# Compute_Module_EXT_INTERFACES.net
KiCad netlist of a schematic drawn in Altium Designer
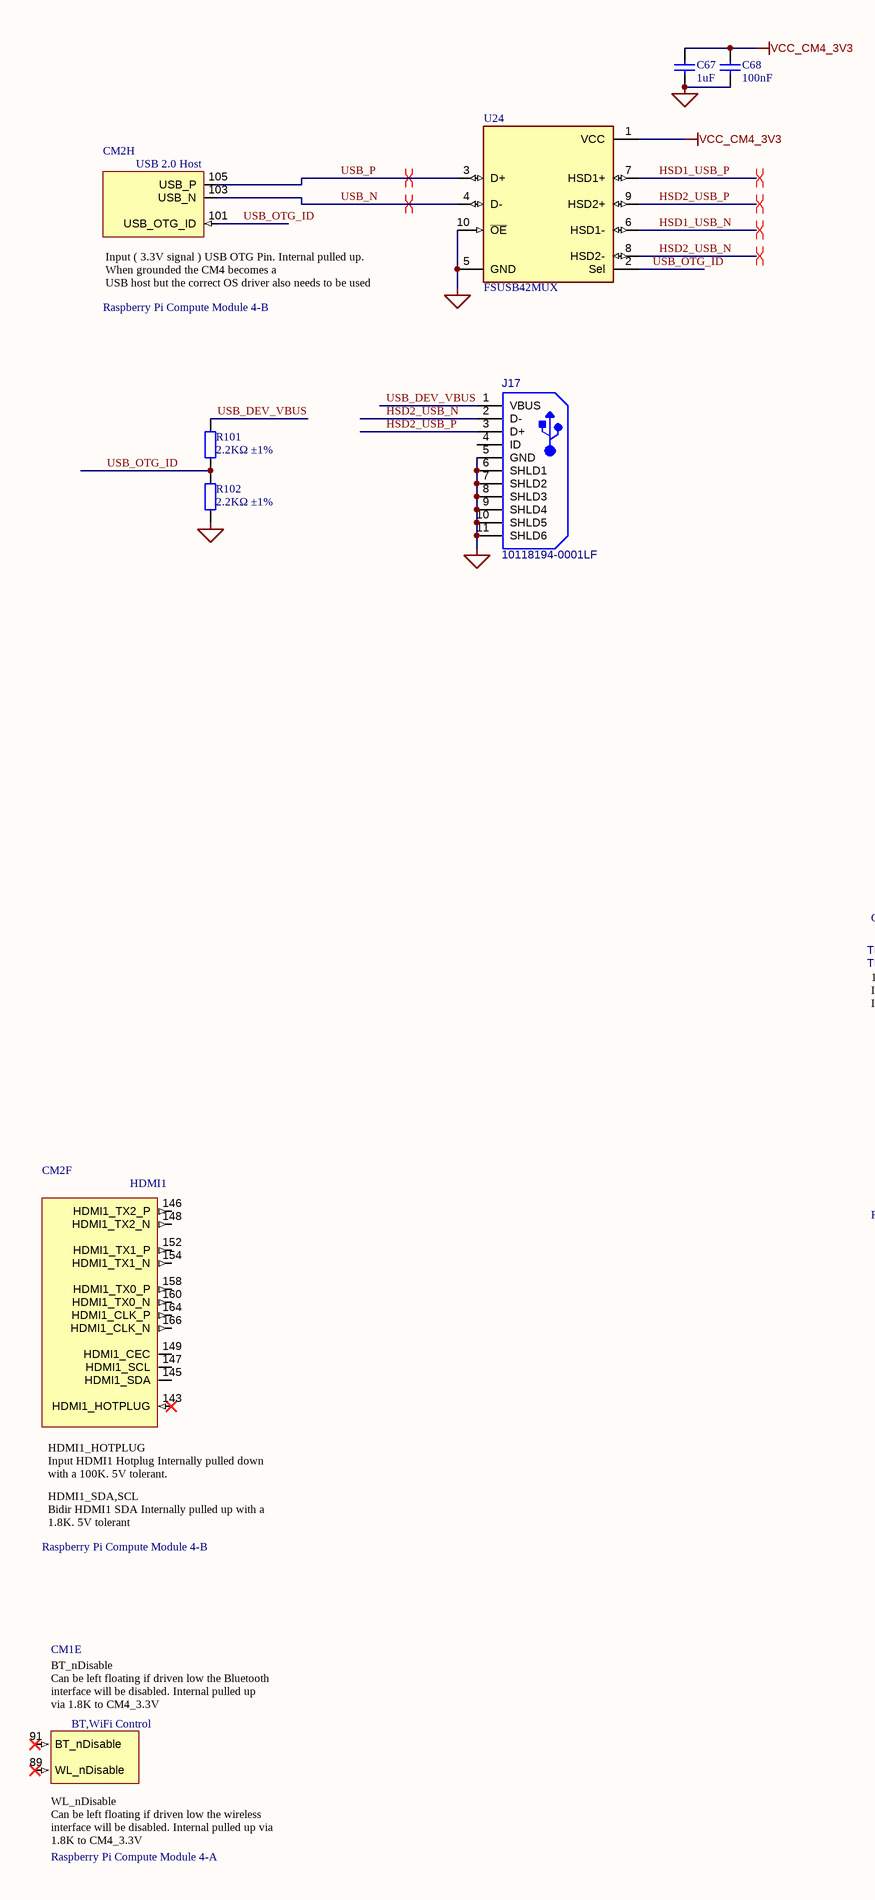
[diagram p0: Compute_Module_EXT_INTERFACES.SchDoc, left]
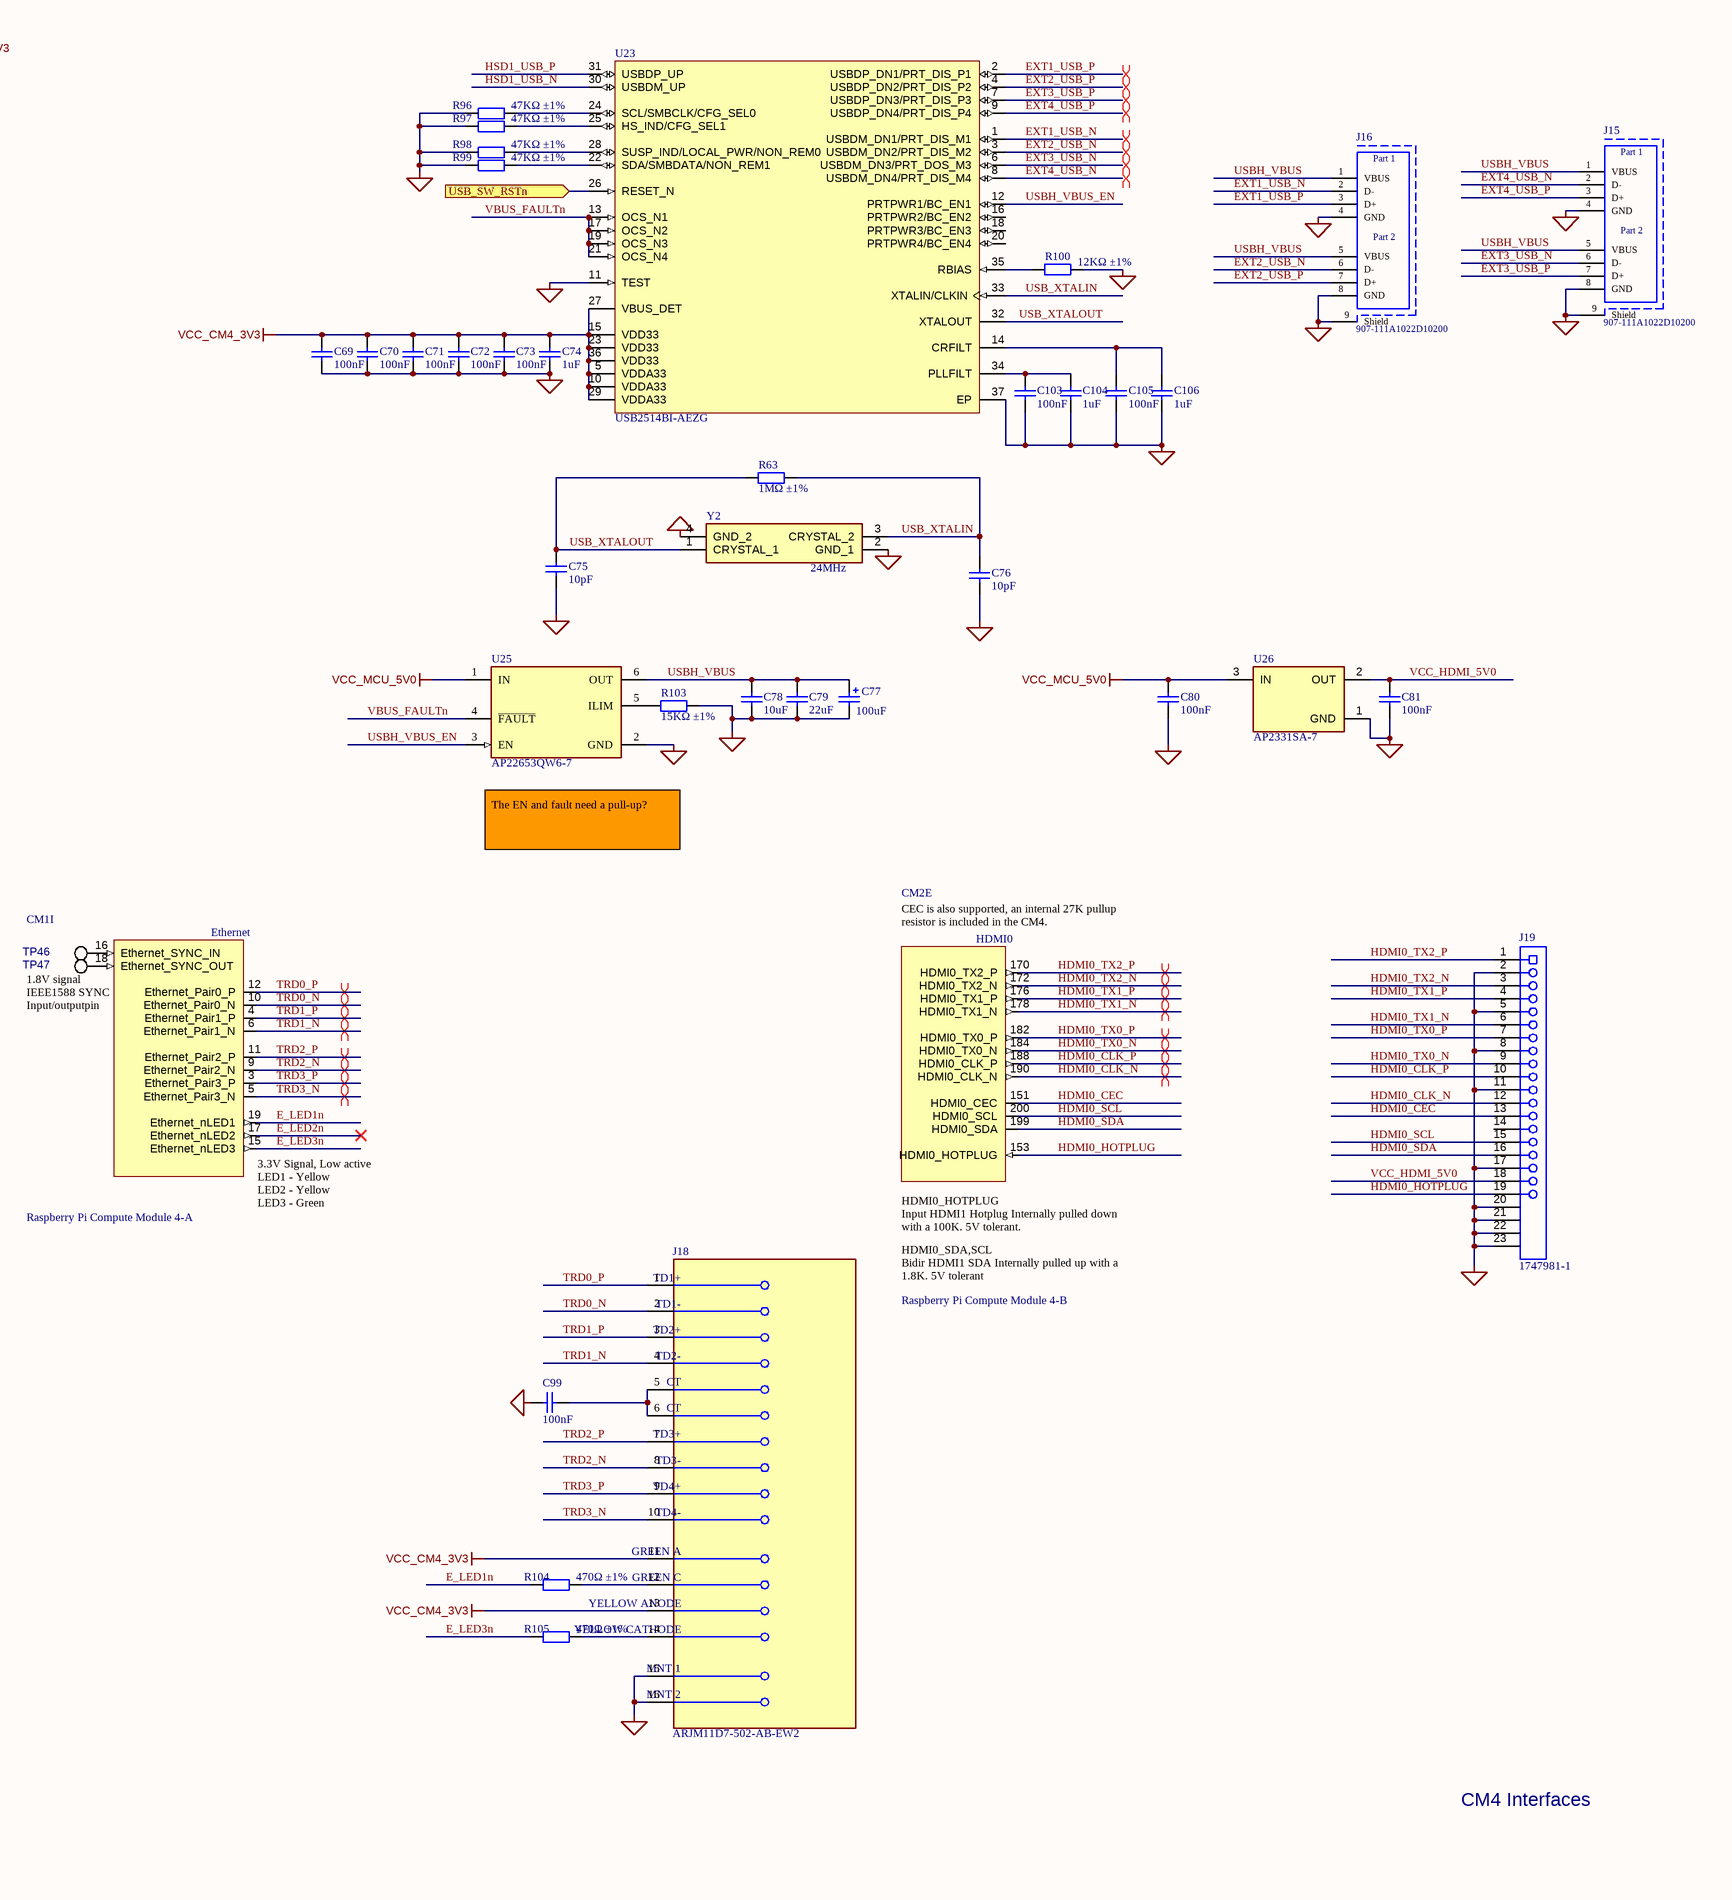
[diagram p1: Compute_Module_EXT_INTERFACES.SchDoc, right]

(export (version "E")
  (design (tool "Eeschema 10.0.6"))
  (components
    (comp (ref "C67")
      (value "1uF")
      (footprint "0603_C")
      (description "Chip capacitors")
      (fields
        (field (name "MANUFACTURER") "Samsung Electro-Mechanics")
        (field (name "MANUFACTURER PART NUMBER") "CL10A105KB8NNNC")
      )
      (libsource (lib "Cap") (part "0603 1uF (105) 10% 50V"))
    )
    (comp (ref "C68")
      (value "100nF")
      (footprint "0603_C")
      (description "Chip capacitors")
      (fields
        (field (name "MANUFACTURER") "YAGEO")
        (field (name "MANUFACTURER PART NUMBER") "CC0603KRX7R9BB104")
      )
      (libsource (lib "Cap") (part "0603 100nF (104) 10% 50V"))
    )
    (comp (ref "C69")
      (value "100nF")
      (footprint "0603_C")
      (description "Chip capacitors")
      (fields
        (field (name "MANUFACTURER") "YAGEO")
        (field (name "MANUFACTURER PART NUMBER") "CC0603KRX7R9BB104")
      )
      (libsource (lib "Cap") (part "0603 100nF (104) 10% 50V"))
    )
    (comp (ref "C70")
      (value "100nF")
      (footprint "0603_C")
      (description "Chip capacitors")
      (fields
        (field (name "MANUFACTURER") "YAGEO")
        (field (name "MANUFACTURER PART NUMBER") "CC0603KRX7R9BB104")
      )
      (libsource (lib "Cap") (part "0603 100nF (104) 10% 50V"))
    )
    (comp (ref "C71")
      (value "100nF")
      (footprint "0603_C")
      (description "Chip capacitors")
      (fields
        (field (name "MANUFACTURER") "YAGEO")
        (field (name "MANUFACTURER PART NUMBER") "CC0603KRX7R9BB104")
      )
      (libsource (lib "Cap") (part "0603 100nF (104) 10% 50V"))
    )
    (comp (ref "C72")
      (value "100nF")
      (footprint "0603_C")
      (description "Chip capacitors")
      (fields
        (field (name "MANUFACTURER") "YAGEO")
        (field (name "MANUFACTURER PART NUMBER") "CC0603KRX7R9BB104")
      )
      (libsource (lib "Cap") (part "0603 100nF (104) 10% 50V"))
    )
    (comp (ref "C73")
      (value "100nF")
      (footprint "0603_C")
      (description "Chip capacitors")
      (fields
        (field (name "MANUFACTURER") "YAGEO")
        (field (name "MANUFACTURER PART NUMBER") "CC0603KRX7R9BB104")
      )
      (libsource (lib "Cap") (part "0603 100nF (104) 10% 50V"))
    )
    (comp (ref "C74")
      (value "1uF")
      (footprint "0603_C")
      (description "Chip capacitors")
      (fields
        (field (name "MANUFACTURER") "Samsung Electro-Mechanics")
        (field (name "MANUFACTURER PART NUMBER") "CL10A105KB8NNNC")
      )
      (libsource (lib "Cap") (part "0603 1uF (105) 10% 50V"))
    )
    (comp (ref "C75")
      (value "10pF")
      (footprint "0603_C")
      (description "Chip capacitors")
      (fields
        (field (name "MANUFACTURER") "Samsung Electro-Mechanics")
        (field (name "PARTNUMBER") "CL10C100JB8NNNC")
      )
      (libsource (lib "Cap") (part "0603 10pF (100) 5% 50V"))
    )
    (comp (ref "C76")
      (value "10pF")
      (footprint "0603_C")
      (description "Chip capacitors")
      (fields
        (field (name "MANUFACTURER") "Samsung Electro-Mechanics")
        (field (name "PARTNUMBER") "CL10C100JB8NNNC")
      )
      (libsource (lib "Cap") (part "0603 10pF (100) 5% 50V"))
    )
    (comp (ref "C77")
      (value "100uF")
      (footprint "WCAP-ASLI_D6.3H7.7")
      (fields
        (field (name "MANUFACTURER") "Capxon International Elec")
        (field (name "MANUFACTURER PART NUMBER") "HV101M035E077ETR")
      )
      (libsource (lib "IQAnalog") (part "865080445010"))
    )
    (comp (ref "C78")
      (value "10uF")
      (footprint "1206_C")
      (description "Chip capacitors")
      (fields
        (field (name "MANUFACTURER") "Samsung Electro-Mechanics")
        (field (name "MANUFACTURER PART NUMBER") "CL31A106KBHNNNE")
      )
      (libsource (lib "Cap") (part "1206 10uF (106) 10% 50V"))
    )
    (comp (ref "C79")
      (value "22uF")
      (footprint "0805_C")
      (description "Chip capacitors")
      (fields
        (field (name "MANUFACTURER") "Samsung Electro-Mechanics")
        (field (name "PARTNUMBER") "CL21A226MAQNNNE")
      )
      (libsource (lib "Cap") (part "0805 22uF (226) 20% 25V"))
    )
    (comp (ref "C80")
      (value "100nF")
      (footprint "0603_C")
      (description "Chip capacitors")
      (fields
        (field (name "MANUFACTURER") "YAGEO")
        (field (name "MANUFACTURER PART NUMBER") "CC0603KRX7R9BB104")
      )
      (libsource (lib "Cap") (part "0603 100nF (104) 10% 50V"))
    )
    (comp (ref "C81")
      (value "100nF")
      (footprint "0603_C")
      (description "Chip capacitors")
      (fields
        (field (name "MANUFACTURER") "YAGEO")
        (field (name "MANUFACTURER PART NUMBER") "CC0603KRX7R9BB104")
      )
      (libsource (lib "Cap") (part "0603 100nF (104) 10% 50V"))
    )
    (comp (ref "C99")
      (value "100nF")
      (footprint "0603_C")
      (description "Chip capacitors")
      (fields
        (field (name "MANUFACTURER") "YAGEO")
        (field (name "MANUFACTURER PART NUMBER") "CC0603KRX7R9BB104")
      )
      (libsource (lib "Cap") (part "0603 100nF (104) 10% 50V"))
    )
    (comp (ref "C103")
      (value "100nF")
      (footprint "0603_C")
      (description "Chip capacitors")
      (fields
        (field (name "MANUFACTURER") "YAGEO")
        (field (name "MANUFACTURER PART NUMBER") "CC0603KRX7R9BB104")
      )
      (libsource (lib "Cap") (part "0603 100nF (104) 10% 50V"))
    )
    (comp (ref "C104")
      (value "1uF")
      (footprint "0603_C")
      (description "Chip capacitors")
      (fields
        (field (name "MANUFACTURER") "Samsung Electro-Mechanics")
        (field (name "MANUFACTURER PART NUMBER") "CL10A105KB8NNNC")
      )
      (libsource (lib "Cap") (part "0603 1uF (105) 10% 50V"))
    )
    (comp (ref "C105")
      (value "100nF")
      (footprint "0603_C")
      (description "Chip capacitors")
      (fields
        (field (name "MANUFACTURER") "YAGEO")
        (field (name "MANUFACTURER PART NUMBER") "CC0603KRX7R9BB104")
      )
      (libsource (lib "Cap") (part "0603 100nF (104) 10% 50V"))
    )
    (comp (ref "C106")
      (value "1uF")
      (footprint "0603_C")
      (description "Chip capacitors")
      (fields
        (field (name "MANUFACTURER") "Samsung Electro-Mechanics")
        (field (name "MANUFACTURER PART NUMBER") "CL10A105KB8NNNC")
      )
      (libsource (lib "Cap") (part "0603 1uF (105) 10% 50V"))
    )
    (comp (ref "CM1")
      (value "Raspberry Pi Compute Module 4-A")
      (footprint "DF40HC30100DS04V51")
      (description "Raspberry Pi Compute Module 4 Pins 1-100 (Connector A)")
      (fields
        (field (name "MANUFACTURER") "Hirose")
        (field (name "MANUFACTURER PART NUMBER") "DF40HC(3.0)-100DS-0.4V(51)")
      )
      (libsource (lib "Sienci_Labs") (part "CM4_Module_A"))
    )
    (comp (ref "CM2")
      (value "Raspberry Pi Compute Module 4-B")
      (footprint "DF40HC30100DS04V51 - p101-200")
      (description "Raspberry Pi Compute Module 4 Pins 101-200 (Connector B)")
      (fields
        (field (name "MANUFACTURER") "Hirose")
        (field (name "MANUFACTURER PART NUMBER") "DF40HC(3.0)-100DS-0.4V(51)")
      )
      (libsource (lib "Sienci_Labs") (part "CM4_Module_B"))
    )
    (comp (ref "J15")
      (value "907-111A1022D10200")
      (footprint "USB-A-TH_USB-M-51")
      (description "USB 2.0 2 8 Female Type-A Plugin USB Connectors ROHS")
      (fields (field (name "MANUFACTURER") "Jing Extension of the Electronic Co."))
      (libsource (lib "Sienci_Labs") (part "907-111A1022D10200"))
    )
    (comp (ref "J16")
      (value "907-111A1022D10200")
      (footprint "USB-A-TH_USB-M-51")
      (description "USB 2.0 2 8 Female Type-A Plugin USB Connectors ROHS")
      (fields (field (name "MANUFACTURER") "Jing Extension of the Electronic Co."))
      (libsource (lib "Sienci_Labs") (part "907-111A1022D10200"))
    )
    (comp (ref "J17")
      (value "10118194-0001LF")
      (footprint "FCI-10118194-0001LF-5_V")
      (description "CONN RCPT USB2.0 MICRO B SMD R/A")
      (fields (field (name "MANUFACTURER") "Amphenol ICC (FCI)"))
      (libsource (lib "Sienci_Labs") (part "USB-5-6SHLD"))
    )
    (comp (ref "J18")
      (value "ARJM11D7-502-AB-EW2")
      (footprint "FP-ARJM11D7-502-AB-EW2-MFG")
      (description "1 Port RJ45Through Hole 10/100/1000 Base-T, AutoMDIX")
      (fields (field (name "MANUFACTURER") "Abracon LLC"))
      (libsource (lib "Sienci_Labs") (part "ARJM11D7-502-AB-EW2"))
    )
    (comp (ref "J19")
      (value "1747981-1")
      (footprint "TE-1747981-1_V")
      (description "HDMI Receptacle, Pitch 0.5 mm, 19 Position, Height 6.38 mm, RoHS, Tape and Reel")
      (fields (field (name "TOLERANCE") "1%") (field (name "MANUFACTURER") "TE Connectivity"))
      (libsource (lib "Altium Content Vault") (part "CN-1P-F-HD19"))
    )
    (comp (ref "R63")
      (value "1MΩ ±1%")
      (footprint "0402_R")
      (description "Chip resistor")
      (fields (field (name "MANUFACTURER") "Uniroyal Elec") (field (name "PARTNUMBER") "0402WGF1004TCE"))
      (libsource (lib "RES") (part "0402 1M (1004) 1%"))
    )
    (comp (ref "R96")
      (value "47KΩ ±1%")
      (footprint "0402_R")
      (description "Chip resistor")
      (fields (field (name "MANUFACTURER") "Uniroyal Elec") (field (name "PARTNUMBER") "0402WGF4702TCE"))
      (libsource (lib "RES") (part "0402 47K (4702) 1%"))
    )
    (comp (ref "R97")
      (value "47KΩ ±1%")
      (footprint "0402_R")
      (description "Chip resistor")
      (fields (field (name "MANUFACTURER") "Uniroyal Elec") (field (name "PARTNUMBER") "0402WGF4702TCE"))
      (libsource (lib "RES") (part "0402 47K (4702) 1%"))
    )
    (comp (ref "R98")
      (value "47KΩ ±1%")
      (footprint "0402_R")
      (description "Chip resistor")
      (fields (field (name "MANUFACTURER") "Uniroyal Elec") (field (name "PARTNUMBER") "0402WGF4702TCE"))
      (libsource (lib "RES") (part "0402 47K (4702) 1%"))
    )
    (comp (ref "R99")
      (value "47KΩ ±1%")
      (footprint "0402_R")
      (description "Chip resistor")
      (fields (field (name "MANUFACTURER") "Uniroyal Elec") (field (name "PARTNUMBER") "0402WGF4702TCE"))
      (libsource (lib "RES") (part "0402 47K (4702) 1%"))
    )
    (comp (ref "R100")
      (value "12KΩ ±1%")
      (footprint "0402_R")
      (description "Chip resistor")
      (fields (field (name "MANUFACTURER") "Uniroyal Elec") (field (name "PARTNUMBER") "0402WGF1202TCE"))
      (libsource (lib "RES") (part "0402 12K (1202) 1%"))
    )
    (comp (ref "R101")
      (value "2.2KΩ ±1%")
      (footprint "0402_R")
      (description "Chip resistor")
      (fields (field (name "MANUFACTURER") "Uniroyal Elec") (field (name "PARTNUMBER") "0402WGF2201TCE"))
      (libsource (lib "RES") (part "0402 2.2K (2201) 1%"))
    )
    (comp (ref "R102")
      (value "2.2KΩ ±1%")
      (footprint "0402_R")
      (description "Chip resistor")
      (fields (field (name "MANUFACTURER") "Uniroyal Elec") (field (name "PARTNUMBER") "0402WGF2201TCE"))
      (libsource (lib "RES") (part "0402 2.2K (2201) 1%"))
    )
    (comp (ref "R103")
      (value "15KΩ ±1%")
      (footprint "0402_R")
      (description "Chip resistor")
      (fields (field (name "MANUFACTURER") "Uniroyal Elec") (field (name "PARTNUMBER") "0402WGF1502TCE"))
      (libsource (lib "RES") (part "0402 15K (1502) 1%"))
    )
    (comp (ref "R104")
      (value "470Ω ±1%")
      (footprint "0402_R")
      (description "Chip resistor")
      (fields (field (name "MANUFACTURER") "Uniroyal Elec") (field (name "PARTNUMBER") "0402WGF4700TCE"))
      (libsource (lib "RES") (part "0402 470R (4700) 1%"))
    )
    (comp (ref "R105")
      (value "470Ω ±1%")
      (footprint "0402_R")
      (description "Chip resistor")
      (fields (field (name "MANUFACTURER") "Uniroyal Elec") (field (name "PARTNUMBER") "0402WGF4700TCE"))
      (libsource (lib "RES") (part "0402 470R (4700) 1%"))
    )
    (comp (ref "TP46")
      (value "TESTPOINT")
      (footprint "TP/SMALL")
      (description "Test Point")
      (libsource (lib "Sienci_Labs") (part "TESTPOINT"))
    )
    (comp (ref "TP47")
      (value "TESTPOINT")
      (footprint "TP/SMALL")
      (description "Test Point")
      (libsource (lib "Sienci_Labs") (part "TESTPOINT"))
    )
    (comp (ref "U23")
      (value "USB2514BI-AEZG")
      (footprint "QFN50P600X600X100-37N-D")
      (description "Microchip USB2514BI-AEZG; USB Controller; 480Mbit/s; USB 2.0; 3.3 V; 36-Pin QFN")
      (fields (field (name "MANUFACTURER") "Microchip"))
      (libsource (lib "Sienci_Labs") (part "USB2514BI-AEZG"))
    )
    (comp (ref "U24")
      (value "FSUSB42MUX")
      (footprint "SOP50P490X110-10N")
      (description "FSUSB42 Series DPDT 4.3 V 480 Mbps SMT Hi Speed USB 2.0 Switch - MSOP-10")
      (fields (field (name "VOLTAGE") "4.3V") (field (name "MANUFACTURER") "ON Semiconductor / Fairchild"))
      (libsource (lib "Sienci_Labs") (part "FSUSB42MUX"))
    )
    (comp (ref "U25")
      (value "AP22653QW6-7")
      (footprint "SOT95P280X145-6N")
      (description "ESDA Series 14.2 V 90 pF Automotive Dual Transil ESD Array - SOT-23")
      (fields (field (name "MANUFACTURER") "Diodes"))
      (libsource (lib "Sienci_Labs") (part "AP22653QW6-7"))
    )
    (comp (ref "U26")
      (value "AP2331SA-7")
      (footprint "SOT91P240X120-3N")
      (description "AP2331 Series Single Channel 0.2 A Current-Limited Load Switch - SOT-23")
      (fields (field (name "MANUFACTURER") "Diodes"))
      (libsource (lib "Sienci_Labs") (part "AP2331SA-7"))
    )
    (comp (ref "Y2")
      (value "24MHz")
      (footprint "YSX321SL")
      (description "24MHz SMD Crystal Resonator 20pF 60Ω ±10ppm -40℃~+85℃ SMD3225-4P Crystals ROHS")
      (fields (field (name "MANUFACTURER_PART_NUMBER") "S3224000201060") (field (name "MANUFACTURER") "JGHC"))
      (libsource (lib "Sienci_Labs") (part "S3224000201060"))
    )
  )
  (nets
    (net (code "1") (name "/EXT1_USB_N") (class "Default")
      (node (ref "J16") (pin "2") (pinfunction "D-_2") (pintype "passive"))
      (node (ref "U23") (pin "1") (pinfunction "USBDM_DN1/PRT_DIS_M1_1") (pintype "bidirectional"))
    )
    (net (code "2") (name "/EXT1_USB_P") (class "Default")
      (node (ref "J16") (pin "3") (pinfunction "D+_3") (pintype "passive"))
      (node (ref "U23") (pin "2") (pinfunction "USBDP_DN1/PRT_DIS_P1_2") (pintype "bidirectional"))
    )
    (net (code "3") (name "/EXT2_USB_N") (class "Default")
      (node (ref "J16") (pin "6") (pinfunction "D-_6") (pintype "passive"))
      (node (ref "U23") (pin "3") (pinfunction "USBDM_DN2/PRT_DIS_M2_3") (pintype "bidirectional"))
    )
    (net (code "4") (name "/EXT2_USB_P") (class "Default")
      (node (ref "J16") (pin "7") (pinfunction "D+_7") (pintype "passive"))
      (node (ref "U23") (pin "4") (pinfunction "USBDP_DN2/PRT_DIS_P2_4") (pintype "bidirectional"))
    )
    (net (code "5") (name "/EXT3_USB_N") (class "Default")
      (node (ref "J15") (pin "6") (pinfunction "D-_6") (pintype "passive"))
      (node (ref "U23") (pin "6") (pinfunction "USBDM_DN3/PRT_DOS_M3_6") (pintype "bidirectional"))
    )
    (net (code "6") (name "/EXT3_USB_P") (class "Default")
      (node (ref "J15") (pin "7") (pinfunction "D+_7") (pintype "passive"))
      (node (ref "U23") (pin "7") (pinfunction "USBDP_DN3/PRT_DIS_P3_7") (pintype "bidirectional"))
    )
    (net (code "7") (name "/EXT4_USB_N") (class "Default")
      (node (ref "J15") (pin "2") (pinfunction "D-_2") (pintype "passive"))
      (node (ref "U23") (pin "8") (pinfunction "USBDM_DN4/PRT_DIS_M4_8") (pintype "bidirectional"))
    )
    (net (code "8") (name "/EXT4_USB_P") (class "Default")
      (node (ref "J15") (pin "3") (pinfunction "D+_3") (pintype "passive"))
      (node (ref "U23") (pin "9") (pinfunction "USBDP_DN4/PRT_DIS_P4_9") (pintype "bidirectional"))
    )
    (net (code "9") (name "/E_LED1n") (class "Default")
      (node (ref "CM1") (pin "19") (pinfunction "Ethernet_nLED1_19") (pintype "output"))
      (node (ref "R104") (pin "1") (pinfunction "1_1") (pintype "passive"))
    )
    (net (code "10") (name "/E_LED2n") (class "Default")
      (node (ref "CM1") (pin "17") (pinfunction "Ethernet_nLED2_17") (pintype "output+no_connect"))
    )
    (net (code "11") (name "/E_LED3n") (class "Default")
      (node (ref "CM1") (pin "15") (pinfunction "Ethernet_nLED3_15") (pintype "output"))
      (node (ref "R105") (pin "1") (pinfunction "1_1") (pintype "passive"))
    )
    (net (code "12") (name "/HDMI0_CEC") (class "Default")
      (node (ref "CM2") (pin "151") (pinfunction "HDMI0_CEC_151") (pintype "open_collector"))
      (node (ref "J19") (pin "13") (pinfunction "13_13") (pintype "passive"))
    )
    (net (code "13") (name "/HDMI0_CLK_N") (class "Default")
      (node (ref "CM2") (pin "190") (pinfunction "HDMI0_CLK_N_190") (pintype "output"))
      (node (ref "J19") (pin "12") (pinfunction "12_12") (pintype "passive"))
    )
    (net (code "14") (name "/HDMI0_CLK_P") (class "Default")
      (node (ref "CM2") (pin "188") (pinfunction "HDMI0_CLK_P_188") (pintype "output"))
      (node (ref "J19") (pin "10") (pinfunction "10_10") (pintype "passive"))
    )
    (net (code "15") (name "/HDMI0_HOTPLUG") (class "Default")
      (node (ref "CM2") (pin "153") (pinfunction "HDMI0_HOTPLUG_153") (pintype "input"))
      (node (ref "J19") (pin "19") (pinfunction "19_19") (pintype "passive"))
    )
    (net (code "16") (name "/HDMI0_SCL") (class "Default")
      (node (ref "CM2") (pin "200") (pinfunction "HDMI0_SCL_200") (pintype "open_collector"))
      (node (ref "J19") (pin "15") (pinfunction "15_15") (pintype "passive"))
    )
    (net (code "17") (name "/HDMI0_SDA") (class "Default")
      (node (ref "CM2") (pin "199") (pinfunction "HDMI0_SDA_199") (pintype "bidirectional"))
      (node (ref "J19") (pin "16") (pinfunction "16_16") (pintype "passive"))
    )
    (net (code "18") (name "/HDMI0_TX0_N") (class "Default")
      (node (ref "CM2") (pin "184") (pinfunction "HDMI0_TX0_N_184") (pintype "output"))
      (node (ref "J19") (pin "9") (pinfunction "9_9") (pintype "passive"))
    )
    (net (code "19") (name "/HDMI0_TX0_P") (class "Default")
      (node (ref "CM2") (pin "182") (pinfunction "HDMI0_TX0_P_182") (pintype "output"))
      (node (ref "J19") (pin "7") (pinfunction "7_7") (pintype "passive"))
    )
    (net (code "20") (name "/HDMI0_TX1_N") (class "Default")
      (node (ref "CM2") (pin "178") (pinfunction "HDMI0_TX1_N_178") (pintype "output"))
      (node (ref "J19") (pin "6") (pinfunction "6_6") (pintype "passive"))
    )
    (net (code "21") (name "/HDMI0_TX1_P") (class "Default")
      (node (ref "CM2") (pin "176") (pinfunction "HDMI0_TX1_P_176") (pintype "output"))
      (node (ref "J19") (pin "4") (pinfunction "4_4") (pintype "passive"))
    )
    (net (code "22") (name "/HDMI0_TX2_N") (class "Default")
      (node (ref "CM2") (pin "172") (pinfunction "HDMI0_TX2_N_172") (pintype "output"))
      (node (ref "J19") (pin "3") (pinfunction "3_3") (pintype "passive"))
    )
    (net (code "23") (name "/HDMI0_TX2_P") (class "Default")
      (node (ref "CM2") (pin "170") (pinfunction "HDMI0_TX2_P_170") (pintype "output"))
      (node (ref "J19") (pin "1") (pinfunction "1_1") (pintype "passive"))
    )
    (net (code "24") (name "/HSD1_USB_N") (class "Default")
      (node (ref "U23") (pin "30") (pinfunction "USBDM_UP_30") (pintype "bidirectional"))
      (node (ref "U24") (pin "6") (pinfunction "HSD1-_6") (pintype "bidirectional"))
    )
    (net (code "25") (name "/HSD1_USB_P") (class "Default")
      (node (ref "U23") (pin "31") (pinfunction "USBDP_UP_31") (pintype "bidirectional"))
      (node (ref "U24") (pin "7") (pinfunction "HSD1+_7") (pintype "bidirectional"))
    )
    (net (code "26") (name "/HSD2_USB_N") (class "Default")
      (node (ref "J17") (pin "2") (pinfunction "D-_2") (pintype "passive"))
      (node (ref "U24") (pin "8") (pinfunction "HSD2-_8") (pintype "bidirectional"))
    )
    (net (code "27") (name "/HSD2_USB_P") (class "Default")
      (node (ref "J17") (pin "3") (pinfunction "D+_3") (pintype "passive"))
      (node (ref "U24") (pin "9") (pinfunction "HSD2+_9") (pintype "bidirectional"))
    )
    (net (code "28") (name "/TRD0_N") (class "Default")
      (node (ref "CM1") (pin "10") (pinfunction "Ethernet_Pair0_N_10") (pintype "passive"))
      (node (ref "J18") (pin "2") (pinfunction "TD1-_2") (pintype "passive"))
    )
    (net (code "29") (name "/TRD0_P") (class "Default")
      (node (ref "CM1") (pin "12") (pinfunction "Ethernet_Pair0_P_12") (pintype "passive"))
      (node (ref "J18") (pin "1") (pinfunction "TD1+_1") (pintype "passive"))
    )
    (net (code "30") (name "/TRD1_N") (class "Default")
      (node (ref "CM1") (pin "6") (pinfunction "Ethernet_Pair1_N_6") (pintype "passive"))
      (node (ref "J18") (pin "4") (pinfunction "TD2-_4") (pintype "passive"))
    )
    (net (code "31") (name "/TRD1_P") (class "Default")
      (node (ref "CM1") (pin "4") (pinfunction "Ethernet_Pair1_P_4") (pintype "passive"))
      (node (ref "J18") (pin "3") (pinfunction "TD2+_3") (pintype "passive"))
    )
    (net (code "32") (name "/TRD2_N") (class "Default")
      (node (ref "CM1") (pin "9") (pinfunction "Ethernet_Pair2_N_9") (pintype "passive"))
      (node (ref "J18") (pin "8") (pinfunction "TD3-_8") (pintype "passive"))
    )
    (net (code "33") (name "/TRD2_P") (class "Default")
      (node (ref "CM1") (pin "11") (pinfunction "Ethernet_Pair2_P_11") (pintype "passive"))
      (node (ref "J18") (pin "7") (pinfunction "TD3+_7") (pintype "passive"))
    )
    (net (code "34") (name "/TRD3_N") (class "Default")
      (node (ref "CM1") (pin "5") (pinfunction "Ethernet_Pair3_N_5") (pintype "passive"))
      (node (ref "J18") (pin "10") (pinfunction "TD4-_10") (pintype "passive"))
    )
    (net (code "35") (name "/TRD3_P") (class "Default")
      (node (ref "CM1") (pin "3") (pinfunction "Ethernet_Pair3_P_3") (pintype "passive"))
      (node (ref "J18") (pin "9") (pinfunction "TD4+_9") (pintype "passive"))
    )
    (net (code "36") (name "/USBH_VBUS") (class "Default")
      (node (ref "C77") (pin "1") (pinfunction "P_1") (pintype "passive"))
      (node (ref "C78") (pin "2") (pinfunction "2_2") (pintype "passive"))
      (node (ref "C79") (pin "2") (pinfunction "2_2") (pintype "passive"))
      (node (ref "J15") (pin "1") (pinfunction "VBUS_1") (pintype "passive"))
      (node (ref "J15") (pin "5") (pinfunction "VBUS_5") (pintype "passive"))
      (node (ref "J16") (pin "1") (pinfunction "VBUS_1") (pintype "passive"))
      (node (ref "J16") (pin "5") (pinfunction "VBUS_5") (pintype "passive"))
      (node (ref "U25") (pin "6") (pinfunction "OUT_6") (pintype "passive"))
    )
    (net (code "37") (name "/USBH_VBUS_EN") (class "Default")
      (node (ref "U23") (pin "12") (pinfunction "PRTPWR1/BC_EN1_12") (pintype "bidirectional"))
      (node (ref "U25") (pin "3") (pinfunction "EN_3") (pintype "input"))
    )
    (net (code "38") (name "/USB_DEV_VBUS") (class "Default")
      (node (ref "J17") (pin "1") (pinfunction "VBUS_1") (pintype "passive"))
      (node (ref "R101") (pin "2") (pinfunction "2_2") (pintype "passive"))
    )
    (net (code "39") (name "/USB_N") (class "Default")
      (node (ref "CM2") (pin "103") (pinfunction "USB_N_103") (pintype "passive"))
      (node (ref "U24") (pin "4") (pinfunction "D-_4") (pintype "bidirectional"))
    )
    (net (code "40") (name "/USB_OTG_ID") (class "Default")
      (node (ref "CM2") (pin "101") (pinfunction "USB_OTG_ID_101") (pintype "input"))
      (node (ref "R101") (pin "1") (pinfunction "1_1") (pintype "passive"))
      (node (ref "R102") (pin "2") (pinfunction "2_2") (pintype "passive"))
      (node (ref "U24") (pin "2") (pinfunction "Sel_2") (pintype "passive"))
    )
    (net (code "41") (name "/USB_P") (class "Default")
      (node (ref "CM2") (pin "105") (pinfunction "USB_P_105") (pintype "passive"))
      (node (ref "U24") (pin "3") (pinfunction "D+_3") (pintype "bidirectional"))
    )
    (net (code "42") (name "/USB_SW_RSTn") (class "Default")
      (node (ref "U23") (pin "26") (pinfunction "RESET_N_26") (pintype "input"))
    )
    (net (code "43") (name "/USB_XTALIN") (class "Default")
      (node (ref "C76") (pin "2") (pinfunction "2_2") (pintype "passive"))
      (node (ref "R63") (pin "2") (pinfunction "2_2") (pintype "passive"))
      (node (ref "U23") (pin "33") (pinfunction "XTALIN/CLKIN_33") (pintype "input"))
      (node (ref "Y2") (pin "3") (pinfunction "CRYSTAL_2_3") (pintype "passive"))
    )
    (net (code "44") (name "/USB_XTALOUT") (class "Default")
      (node (ref "C75") (pin "2") (pinfunction "2_2") (pintype "passive"))
      (node (ref "R63") (pin "1") (pinfunction "1_1") (pintype "passive"))
      (node (ref "U23") (pin "32") (pinfunction "XTALOUT_32") (pintype "passive"))
      (node (ref "Y2") (pin "1") (pinfunction "CRYSTAL_1_1") (pintype "passive"))
    )
    (net (code "45") (name "/VBUS_FAULTn") (class "Default")
      (node (ref "U23") (pin "13") (pinfunction "OCS_N1_13") (pintype "input"))
      (node (ref "U23") (pin "17") (pinfunction "OCS_N2_17") (pintype "input"))
      (node (ref "U23") (pin "19") (pinfunction "OCS_N3_19") (pintype "input"))
      (node (ref "U23") (pin "21") (pinfunction "OCS_N4_21") (pintype "input"))
      (node (ref "U25") (pin "4") (pinfunction "~{FAULT}_4") (pintype "open_collector"))
    )
    (net (code "46") (name "/VCC_HDMI_5V0") (class "Default")
      (node (ref "C81") (pin "2") (pinfunction "2_2") (pintype "passive"))
      (node (ref "J19") (pin "18") (pinfunction "18_18") (pintype "passive"))
      (node (ref "U26") (pin "2") (pinfunction "OUT_2") (pintype "power_in"))
    )
    (net (code "47") (name "MCU_GND") (class "Default")
      (node (ref "C103") (pin "1") (pinfunction "1_1") (pintype "passive"))
      (node (ref "C104") (pin "1") (pinfunction "1_1") (pintype "passive"))
      (node (ref "C105") (pin "1") (pinfunction "1_1") (pintype "passive"))
      (node (ref "C106") (pin "1") (pinfunction "1_1") (pintype "passive"))
      (node (ref "C67") (pin "1") (pinfunction "1_1") (pintype "passive"))
      (node (ref "C68") (pin "1") (pinfunction "1_1") (pintype "passive"))
      (node (ref "C69") (pin "1") (pinfunction "1_1") (pintype "passive"))
      (node (ref "C70") (pin "1") (pinfunction "1_1") (pintype "passive"))
      (node (ref "C71") (pin "1") (pinfunction "1_1") (pintype "passive"))
      (node (ref "C72") (pin "1") (pinfunction "1_1") (pintype "passive"))
      (node (ref "C73") (pin "1") (pinfunction "1_1") (pintype "passive"))
      (node (ref "C74") (pin "1") (pinfunction "1_1") (pintype "passive"))
      (node (ref "C75") (pin "1") (pinfunction "1_1") (pintype "passive"))
      (node (ref "C76") (pin "1") (pinfunction "1_1") (pintype "passive"))
      (node (ref "C77") (pin "2") (pinfunction "N_2") (pintype "passive"))
      (node (ref "C78") (pin "1") (pinfunction "1_1") (pintype "passive"))
      (node (ref "C79") (pin "1") (pinfunction "1_1") (pintype "passive"))
      (node (ref "C80") (pin "1") (pinfunction "1_1") (pintype "passive"))
      (node (ref "C81") (pin "1") (pinfunction "1_1") (pintype "passive"))
      (node (ref "C99") (pin "2") (pinfunction "2_2") (pintype "passive"))
      (node (ref "J15") (pin "4") (pinfunction "GND_4") (pintype "passive"))
      (node (ref "J15") (pin "8") (pinfunction "GND_8") (pintype "passive"))
      (node (ref "J15") (pin "9") (pinfunction "Shield_9") (pintype "passive"))
      (node (ref "J16") (pin "4") (pinfunction "GND_4") (pintype "passive"))
      (node (ref "J16") (pin "8") (pinfunction "GND_8") (pintype "passive"))
      (node (ref "J16") (pin "9") (pinfunction "Shield_9") (pintype "passive"))
      (node (ref "J17") (pin "10") (pinfunction "SHLD5_10") (pintype "passive"))
      (node (ref "J17") (pin "11") (pinfunction "SHLD6_11") (pintype "passive"))
      (node (ref "J17") (pin "5") (pinfunction "GND_5") (pintype "passive"))
      (node (ref "J17") (pin "6") (pinfunction "SHLD1_6") (pintype "passive"))
      (node (ref "J17") (pin "7") (pinfunction "SHLD2_7") (pintype "passive"))
      (node (ref "J17") (pin "8") (pinfunction "SHLD3_8") (pintype "passive"))
      (node (ref "J17") (pin "9") (pinfunction "SHLD4_9") (pintype "passive"))
      (node (ref "J18") (pin "15") (pinfunction "MNT_1_15") (pintype "passive"))
      (node (ref "J18") (pin "16") (pinfunction "MNT_2_16") (pintype "passive"))
      (node (ref "J19") (pin "11") (pinfunction "11_11") (pintype "passive"))
      (node (ref "J19") (pin "17") (pinfunction "17_17") (pintype "passive"))
      (node (ref "J19") (pin "2") (pinfunction "2_2") (pintype "passive"))
      (node (ref "J19") (pin "20") (pinfunction "SHLD1_20") (pintype "passive"))
      (node (ref "J19") (pin "21") (pinfunction "SHLD2_21") (pintype "passive"))
      (node (ref "J19") (pin "22") (pinfunction "SHLD3_22") (pintype "passive"))
      (node (ref "J19") (pin "23") (pinfunction "SHLD4_23") (pintype "passive"))
      (node (ref "J19") (pin "5") (pinfunction "5_5") (pintype "passive"))
      (node (ref "J19") (pin "8") (pinfunction "8_8") (pintype "passive"))
      (node (ref "R100") (pin "2") (pinfunction "2_2") (pintype "passive"))
      (node (ref "R102") (pin "1") (pinfunction "1_1") (pintype "passive"))
      (node (ref "R103") (pin "2") (pinfunction "2_2") (pintype "passive"))
      (node (ref "R96") (pin "2") (pinfunction "2_2") (pintype "passive"))
      (node (ref "R97") (pin "2") (pinfunction "2_2") (pintype "passive"))
      (node (ref "R98") (pin "2") (pinfunction "2_2") (pintype "passive"))
      (node (ref "R99") (pin "2") (pinfunction "2_2") (pintype "passive"))
      (node (ref "U23") (pin "11") (pinfunction "TEST_11") (pintype "input"))
      (node (ref "U23") (pin "37") (pinfunction "EP_37") (pintype "power_in"))
      (node (ref "U24") (pin "10") (pinfunction "~{OE}_10") (pintype "input"))
      (node (ref "U24") (pin "5") (pinfunction "GND_5") (pintype "power_in"))
      (node (ref "U25") (pin "2") (pinfunction "GND_2") (pintype "power_in"))
      (node (ref "U26") (pin "1") (pinfunction "GND_1") (pintype "power_in"))
      (node (ref "Y2") (pin "2") (pinfunction "GND_1_2") (pintype "passive"))
      (node (ref "Y2") (pin "4") (pinfunction "GND_2_4") (pintype "passive"))
    )
    (net (code "48") (name "Net-(C99-Pad1)") (class "Default")
      (node (ref "C99") (pin "1") (pinfunction "1_1") (pintype "passive"))
      (node (ref "J18") (pin "5") (pinfunction "CT_5") (pintype "passive"))
      (node (ref "J18") (pin "6") (pinfunction "CT_6") (pintype "passive"))
    )
    (net (code "49") (name "Net-(CM1I-Ethernet_SYNC_IN)") (class "Default")
      (node (ref "CM1") (pin "16") (pinfunction "Ethernet_SYNC_IN_16") (pintype "input"))
      (node (ref "TP46") (pin "1") (pintype "passive"))
    )
    (net (code "50") (name "Net-(CM1I-Ethernet_SYNC_OUT)") (class "Default")
      (node (ref "CM1") (pin "18") (pinfunction "Ethernet_SYNC_OUT_18") (pintype "input"))
      (node (ref "TP47") (pin "1") (pintype "passive"))
    )
    (net (code "51") (name "Net-(J18-GREEN_C)") (class "Default")
      (node (ref "J18") (pin "12") (pinfunction "GREEN_C_12") (pintype "passive"))
      (node (ref "R104") (pin "2") (pinfunction "2_2") (pintype "passive"))
    )
    (net (code "52") (name "Net-(J18-YELLOW_CATHODE)") (class "Default")
      (node (ref "J18") (pin "14") (pinfunction "YELLOW_CATHODE_14") (pintype "passive"))
      (node (ref "R105") (pin "2") (pinfunction "2_2") (pintype "passive"))
    )
    (net (code "53") (name "Net-(U23-CRFILT)") (class "Default")
      (node (ref "C105") (pin "2") (pinfunction "2_2") (pintype "passive"))
      (node (ref "C106") (pin "2") (pinfunction "2_2") (pintype "passive"))
      (node (ref "U23") (pin "14") (pinfunction "CRFILT_14") (pintype "passive"))
    )
    (net (code "54") (name "Net-(U23-HS_IND{slash}CFG_SEL1)") (class "Default")
      (node (ref "R97") (pin "1") (pinfunction "1_1") (pintype "passive"))
      (node (ref "U23") (pin "25") (pinfunction "HS_IND/CFG_SEL1_25") (pintype "bidirectional"))
    )
    (net (code "55") (name "Net-(U23-PLLFILT)") (class "Default")
      (node (ref "C103") (pin "2") (pinfunction "2_2") (pintype "passive"))
      (node (ref "C104") (pin "2") (pinfunction "2_2") (pintype "passive"))
      (node (ref "U23") (pin "34") (pinfunction "PLLFILT_34") (pintype "passive"))
    )
    (net (code "56") (name "Net-(U23-RBIAS)") (class "Default")
      (node (ref "R100") (pin "1") (pinfunction "1_1") (pintype "passive"))
      (node (ref "U23") (pin "35") (pinfunction "RBIAS_35") (pintype "input"))
    )
    (net (code "57") (name "Net-(U23-SCL{slash}SMBCLK{slash}CFG_SEL0)") (class "Default")
      (node (ref "R96") (pin "1") (pinfunction "1_1") (pintype "passive"))
      (node (ref "U23") (pin "24") (pinfunction "SCL/SMBCLK/CFG_SEL0_24") (pintype "bidirectional"))
    )
    (net (code "58") (name "Net-(U23-SDA{slash}SMBDATA{slash}NON_REM1)") (class "Default")
      (node (ref "R99") (pin "1") (pinfunction "1_1") (pintype "passive"))
      (node (ref "U23") (pin "22") (pinfunction "SDA/SMBDATA/NON_REM1_22") (pintype "bidirectional"))
    )
    (net (code "59") (name "Net-(U23-SUSP_IND{slash}LOCAL_PWR{slash}NON_REM0)") (class "Default")
      (node (ref "R98") (pin "1") (pinfunction "1_1") (pintype "passive"))
      (node (ref "U23") (pin "28") (pinfunction "SUSP_IND/LOCAL_PWR/NON_REM0_28") (pintype "bidirectional"))
    )
    (net (code "60") (name "Net-(U25-ILIM)") (class "Default")
      (node (ref "R103") (pin "1") (pinfunction "1_1") (pintype "passive"))
      (node (ref "U25") (pin "5") (pinfunction "ILIM_5") (pintype "passive"))
    )
    (net (code "61") (name "VCC_CM4_3V3") (class "Default")
      (node (ref "C67") (pin "2") (pinfunction "2_2") (pintype "passive"))
      (node (ref "C68") (pin "2") (pinfunction "2_2") (pintype "passive"))
      (node (ref "C69") (pin "2") (pinfunction "2_2") (pintype "passive"))
      (node (ref "C70") (pin "2") (pinfunction "2_2") (pintype "passive"))
      (node (ref "C71") (pin "2") (pinfunction "2_2") (pintype "passive"))
      (node (ref "C72") (pin "2") (pinfunction "2_2") (pintype "passive"))
      (node (ref "C73") (pin "2") (pinfunction "2_2") (pintype "passive"))
      (node (ref "C74") (pin "2") (pinfunction "2_2") (pintype "passive"))
      (node (ref "J18") (pin "11") (pinfunction "GREEN_A_11") (pintype "passive"))
      (node (ref "J18") (pin "13") (pinfunction "YELLOW_ANODE_13") (pintype "passive"))
      (node (ref "U23") (pin "10") (pinfunction "VDDA33_10") (pintype "power_in"))
      (node (ref "U23") (pin "15") (pinfunction "VDD33_15") (pintype "power_in"))
      (node (ref "U23") (pin "23") (pinfunction "VDD33_23") (pintype "power_in"))
      (node (ref "U23") (pin "27") (pinfunction "VBUS_DET_27") (pintype "power_in"))
      (node (ref "U23") (pin "29") (pinfunction "VDDA33_29") (pintype "power_in"))
      (node (ref "U23") (pin "36") (pinfunction "VDD33_36") (pintype "power_in"))
      (node (ref "U23") (pin "5") (pinfunction "VDDA33_5") (pintype "power_in"))
      (node (ref "U24") (pin "1") (pinfunction "VCC_1") (pintype "power_in"))
    )
    (net (code "62") (name "VCC_MCU_5V0") (class "Default")
      (node (ref "C80") (pin "2") (pinfunction "2_2") (pintype "passive"))
      (node (ref "U25") (pin "1") (pinfunction "IN_1") (pintype "power_in"))
      (node (ref "U26") (pin "3") (pinfunction "IN_3") (pintype "power_in"))
    )
    (net (code "63") (name "unconnected-(CM1E-BT_nDisable-Pad91)") (class "Default")
      (node (ref "CM1") (pin "91") (pinfunction "BT_nDisable_91") (pintype "input+no_connect"))
    )
    (net (code "64") (name "unconnected-(CM1E-WL_nDisable-Pad89)") (class "Default")
      (node (ref "CM1") (pin "89") (pinfunction "WL_nDisable_89") (pintype "input+no_connect"))
    )
    (net (code "65") (name "unconnected-(CM2F-HDMI1_CEC-Pad149)") (class "Default")
      (node (ref "CM2") (pin "149") (pinfunction "HDMI1_CEC_149") (pintype "open_collector"))
    )
    (net (code "66") (name "unconnected-(CM2F-HDMI1_CLK_N-Pad166)") (class "Default")
      (node (ref "CM2") (pin "166") (pinfunction "HDMI1_CLK_N_166") (pintype "output"))
    )
    (net (code "67") (name "unconnected-(CM2F-HDMI1_CLK_P-Pad164)") (class "Default")
      (node (ref "CM2") (pin "164") (pinfunction "HDMI1_CLK_P_164") (pintype "output"))
    )
    (net (code "68") (name "unconnected-(CM2F-HDMI1_HOTPLUG-Pad143)") (class "Default")
      (node (ref "CM2") (pin "143") (pinfunction "HDMI1_HOTPLUG_143") (pintype "input+no_connect"))
    )
    (net (code "69") (name "unconnected-(CM2F-HDMI1_SCL-Pad147)") (class "Default")
      (node (ref "CM2") (pin "147") (pinfunction "HDMI1_SCL_147") (pintype "open_collector"))
    )
    (net (code "70") (name "unconnected-(CM2F-HDMI1_SDA-Pad145)") (class "Default")
      (node (ref "CM2") (pin "145") (pinfunction "HDMI1_SDA_145") (pintype "bidirectional"))
    )
    (net (code "71") (name "unconnected-(CM2F-HDMI1_TX0_N-Pad160)") (class "Default")
      (node (ref "CM2") (pin "160") (pinfunction "HDMI1_TX0_N_160") (pintype "output"))
    )
    (net (code "72") (name "unconnected-(CM2F-HDMI1_TX0_P-Pad158)") (class "Default")
      (node (ref "CM2") (pin "158") (pinfunction "HDMI1_TX0_P_158") (pintype "output"))
    )
    (net (code "73") (name "unconnected-(CM2F-HDMI1_TX1_N-Pad154)") (class "Default")
      (node (ref "CM2") (pin "154") (pinfunction "HDMI1_TX1_N_154") (pintype "output"))
    )
    (net (code "74") (name "unconnected-(CM2F-HDMI1_TX1_P-Pad152)") (class "Default")
      (node (ref "CM2") (pin "152") (pinfunction "HDMI1_TX1_P_152") (pintype "output"))
    )
    (net (code "75") (name "unconnected-(CM2F-HDMI1_TX2_N-Pad148)") (class "Default")
      (node (ref "CM2") (pin "148") (pinfunction "HDMI1_TX2_N_148") (pintype "output"))
    )
    (net (code "76") (name "unconnected-(CM2F-HDMI1_TX2_P-Pad146)") (class "Default")
      (node (ref "CM2") (pin "146") (pinfunction "HDMI1_TX2_P_146") (pintype "output"))
    )
    (net (code "77") (name "unconnected-(J17-ID-Pad4)") (class "Default")
      (node (ref "J17") (pin "4") (pinfunction "ID_4") (pintype "passive"))
    )
    (net (code "78") (name "unconnected-(J19-Pad14)") (class "Default")
      (node (ref "J19") (pin "14") (pinfunction "14_14") (pintype "passive"))
    )
    (net (code "79") (name "unconnected-(U23-PRTPWR2{slash}BC_EN2-Pad16)") (class "Default")
      (node (ref "U23") (pin "16") (pinfunction "PRTPWR2/BC_EN2_16") (pintype "bidirectional"))
    )
    (net (code "80") (name "unconnected-(U23-PRTPWR3{slash}BC_EN3-Pad18)") (class "Default")
      (node (ref "U23") (pin "18") (pinfunction "PRTPWR3/BC_EN3_18") (pintype "bidirectional"))
    )
    (net (code "81") (name "unconnected-(U23-PRTPWR4{slash}BC_EN4-Pad20)") (class "Default")
      (node (ref "U23") (pin "20") (pinfunction "PRTPWR4/BC_EN4_20") (pintype "bidirectional"))
    )
  )
)
